# irrigation_control_unit.net
KiCad netlist of a schematic drawn in EAGLE
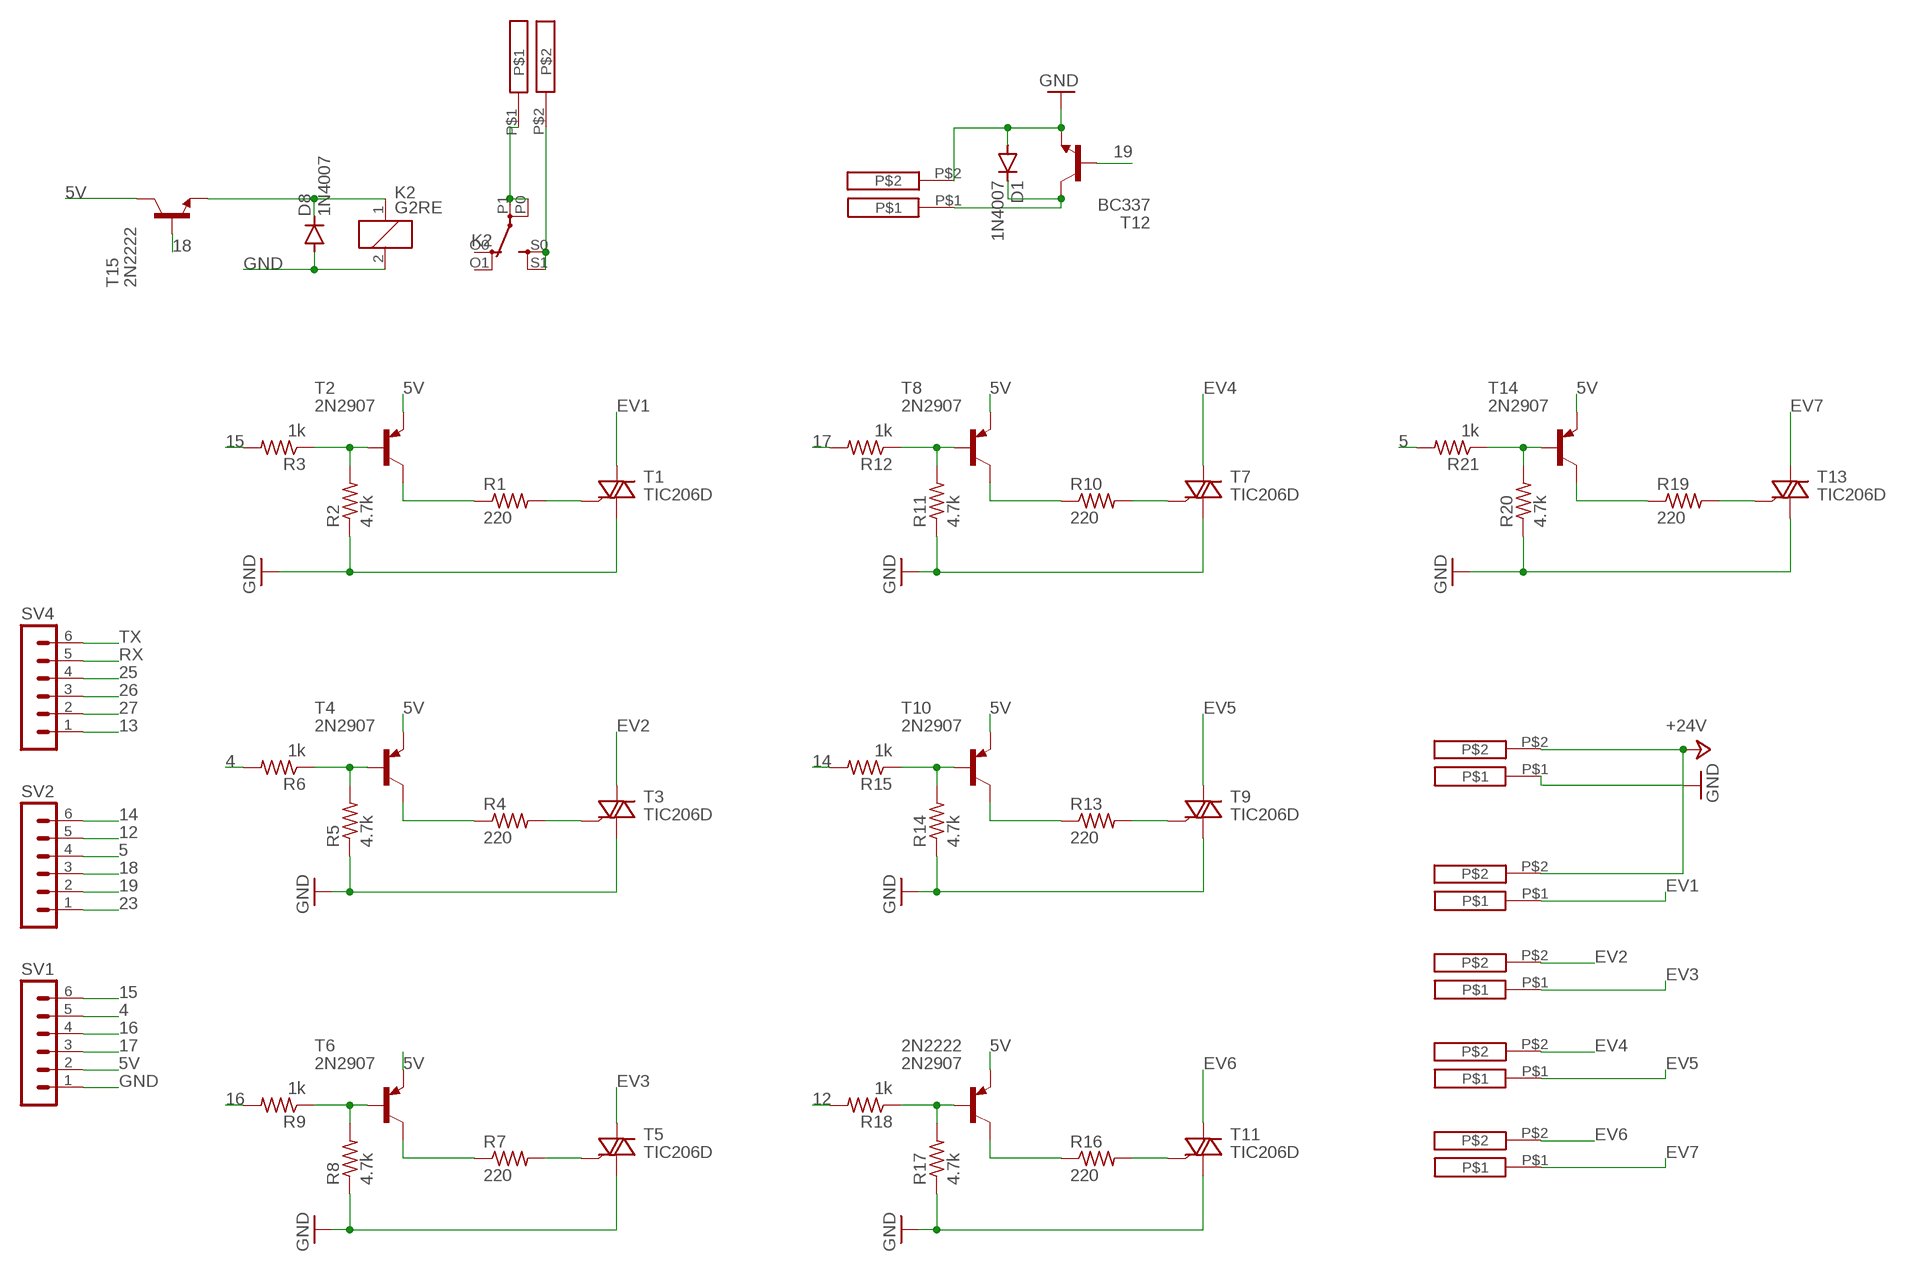
[diagram p0: schematic, sheet 1]

(export (version "E")
  (design (tool "Eeschema 10.0.6"))
  (components
    (comp (ref "2N2222")
      (value "2N2907")
      (footprint "eagle-import:TO92-EBC-OVAL")
      (libsource (lib "eagle-import") (part "2N2907"))
    )
    (comp (ref "D1")
      (value "1N4007")
      (footprint "eagle-import:DO35-7")
      (libsource (lib "eagle-import") (part "1N4148DO35-7"))
    )
    (comp (ref "D8")
      (value "1N4007")
      (footprint "eagle-import:DO35-7")
      (libsource (lib "eagle-import") (part "1N4148DO35-7"))
    )
    (comp (ref "K2")
      (value "G2RE")
      (footprint "eagle-import:G2RE")
      (libsource (lib "eagle-import") (part "G2RE"))
    )
    (comp (ref "R1")
      (value "220")
      (footprint "eagle-import:0204_7")
      (libsource (lib "eagle-import") (part "R-US_0204/7"))
    )
    (comp (ref "R2")
      (value "4.7k")
      (footprint "eagle-import:0204_7")
      (libsource (lib "eagle-import") (part "R-US_0204/7"))
    )
    (comp (ref "R3")
      (value "1k")
      (footprint "eagle-import:0204_7")
      (libsource (lib "eagle-import") (part "R-US_0204/7"))
    )
    (comp (ref "R4")
      (value "220")
      (footprint "eagle-import:0204_7")
      (libsource (lib "eagle-import") (part "R-US_0204/7"))
    )
    (comp (ref "R5")
      (value "4.7k")
      (footprint "eagle-import:0204_7")
      (libsource (lib "eagle-import") (part "R-US_0204/7"))
    )
    (comp (ref "R6")
      (value "1k")
      (footprint "eagle-import:0204_7")
      (libsource (lib "eagle-import") (part "R-US_0204/7"))
    )
    (comp (ref "R7")
      (value "220")
      (footprint "eagle-import:0204_7")
      (libsource (lib "eagle-import") (part "R-US_0204/7"))
    )
    (comp (ref "R8")
      (value "4.7k")
      (footprint "eagle-import:0204_7")
      (libsource (lib "eagle-import") (part "R-US_0204/7"))
    )
    (comp (ref "R9")
      (value "1k")
      (footprint "eagle-import:0204_7")
      (libsource (lib "eagle-import") (part "R-US_0204/7"))
    )
    (comp (ref "R10")
      (value "220")
      (footprint "eagle-import:0204_7")
      (libsource (lib "eagle-import") (part "R-US_0204/7"))
    )
    (comp (ref "R11")
      (value "4.7k")
      (footprint "eagle-import:0204_7")
      (libsource (lib "eagle-import") (part "R-US_0204/7"))
    )
    (comp (ref "R12")
      (value "1k")
      (footprint "eagle-import:0204_7")
      (libsource (lib "eagle-import") (part "R-US_0204/7"))
    )
    (comp (ref "R13")
      (value "220")
      (footprint "eagle-import:0204_7")
      (libsource (lib "eagle-import") (part "R-US_0204/7"))
    )
    (comp (ref "R14")
      (value "4.7k")
      (footprint "eagle-import:0204_7")
      (libsource (lib "eagle-import") (part "R-US_0204/7"))
    )
    (comp (ref "R15")
      (value "1k")
      (footprint "eagle-import:0204_7")
      (libsource (lib "eagle-import") (part "R-US_0204/7"))
    )
    (comp (ref "R16")
      (value "220")
      (footprint "eagle-import:0204_7")
      (libsource (lib "eagle-import") (part "R-US_0204/7"))
    )
    (comp (ref "R17")
      (value "4.7k")
      (footprint "eagle-import:0204_7")
      (libsource (lib "eagle-import") (part "R-US_0204/7"))
    )
    (comp (ref "R18")
      (value "1k")
      (footprint "eagle-import:0204_7")
      (libsource (lib "eagle-import") (part "R-US_0204/7"))
    )
    (comp (ref "R19")
      (value "220")
      (footprint "eagle-import:0204_7")
      (libsource (lib "eagle-import") (part "R-US_0204/7"))
    )
    (comp (ref "R20")
      (value "4.7k")
      (footprint "eagle-import:0204_7")
      (libsource (lib "eagle-import") (part "R-US_0204/7"))
    )
    (comp (ref "R21")
      (value "1k")
      (footprint "eagle-import:0204_7")
      (libsource (lib "eagle-import") (part "R-US_0204/7"))
    )
    (comp (ref "SV1")
      (value "MA06-1")
      (footprint "eagle-import:MA06-1")
      (libsource (lib "eagle-import") (part "MA06-1"))
    )
    (comp (ref "SV2")
      (value "MA06-1")
      (footprint "eagle-import:MA06-1")
      (libsource (lib "eagle-import") (part "MA06-1"))
    )
    (comp (ref "SV4")
      (value "MA06-1")
      (footprint "eagle-import:MA06-1")
      (libsource (lib "eagle-import") (part "MA06-1"))
    )
    (comp (ref "T1")
      (value "TIC206D")
      (footprint "eagle-import:TO220BV")
      (libsource (lib "eagle-import") (part "TIC206D"))
    )
    (comp (ref "T2")
      (value "2N2907")
      (footprint "eagle-import:TO92-EBC-OVAL")
      (libsource (lib "eagle-import") (part "2N2907"))
    )
    (comp (ref "T3")
      (value "TIC206D")
      (footprint "eagle-import:TO220BV")
      (libsource (lib "eagle-import") (part "TIC206D"))
    )
    (comp (ref "T4")
      (value "2N2907")
      (footprint "eagle-import:TO92-EBC-OVAL")
      (libsource (lib "eagle-import") (part "2N2907"))
    )
    (comp (ref "T5")
      (value "TIC206D")
      (footprint "eagle-import:TO220BV")
      (libsource (lib "eagle-import") (part "TIC206D"))
    )
    (comp (ref "T6")
      (value "2N2907")
      (footprint "eagle-import:TO92-EBC-OVAL")
      (libsource (lib "eagle-import") (part "2N2907"))
    )
    (comp (ref "T7")
      (value "TIC206D")
      (footprint "eagle-import:TO220BV")
      (libsource (lib "eagle-import") (part "TIC206D"))
    )
    (comp (ref "T8")
      (value "2N2907")
      (footprint "eagle-import:TO92-EBC-OVAL")
      (libsource (lib "eagle-import") (part "2N2907"))
    )
    (comp (ref "T9")
      (value "TIC206D")
      (footprint "eagle-import:TO220BV")
      (libsource (lib "eagle-import") (part "TIC206D"))
    )
    (comp (ref "T10")
      (value "2N2907")
      (footprint "eagle-import:TO92-EBC-OVAL")
      (libsource (lib "eagle-import") (part "2N2907"))
    )
    (comp (ref "T11")
      (value "TIC206D")
      (footprint "eagle-import:TO220BV")
      (libsource (lib "eagle-import") (part "TIC206D"))
    )
    (comp (ref "T12")
      (value "BC337")
      (footprint "eagle-import:TO92")
      (libsource (lib "eagle-import") (part "BC337"))
    )
    (comp (ref "T13")
      (value "TIC206D")
      (footprint "eagle-import:TO220BV")
      (libsource (lib "eagle-import") (part "TIC206D"))
    )
    (comp (ref "T14")
      (value "2N2907")
      (footprint "eagle-import:TO92-EBC-OVAL")
      (libsource (lib "eagle-import") (part "2N2907"))
    )
    (comp (ref "T15")
      (value "2N2222")
      (footprint "eagle-import:TO92-EBC-OVAL")
      (libsource (lib "eagle-import") (part "2N2222"))
    )
    (comp (ref "U$1")
      (value "2-PIN-7.5-CONNECTOR")
      (footprint "eagle-import:2-PIN-7.5-CONNECTOR")
      (libsource (lib "eagle-import") (part "2-PIN-7.5-CONNECTOR"))
    )
    (comp (ref "U$2")
      (value "2-PIN-7.5-CONNECTOR")
      (footprint "eagle-import:2-PIN-7.5-CONNECTOR")
      (libsource (lib "eagle-import") (part "2-PIN-7.5-CONNECTOR"))
    )
    (comp (ref "U$3")
      (value "2-PIN-7.5-CONNECTOR")
      (footprint "eagle-import:2-PIN-7.5-CONNECTOR")
      (libsource (lib "eagle-import") (part "2-PIN-7.5-CONNECTOR"))
    )
    (comp (ref "U$4")
      (value "2-PIN-7.5-CONNECTOR")
      (footprint "eagle-import:2-PIN-7.5-CONNECTOR")
      (libsource (lib "eagle-import") (part "2-PIN-7.5-CONNECTOR"))
    )
    (comp (ref "U$5")
      (value "2-PIN-7.5-CONNECTOR")
      (footprint "eagle-import:2-PIN-7.5-CONNECTOR")
      (libsource (lib "eagle-import") (part "2-PIN-7.5-CONNECTOR"))
    )
    (comp (ref "U$6")
      (value "2-PIN-7.5-CONNECTOR")
      (footprint "eagle-import:2-PIN-7.5-CONNECTOR")
      (libsource (lib "eagle-import") (part "2-PIN-7.5-CONNECTOR"))
    )
    (comp (ref "U$7")
      (value "2-PIN-7.5-CONNECTOR")
      (footprint "eagle-import:2-PIN-7.5-CONNECTOR")
      (libsource (lib "eagle-import") (part "2-PIN-7.5-CONNECTOR"))
    )
  )
  (nets
    (net (code "1") (name "+24V") (class "Default")
      (node (ref "U$1") (pin "P$2") (pinfunction "P$2_P$2") (pintype "bidirectional"))
      (node (ref "U$2") (pin "P$2") (pinfunction "P$2_P$2") (pintype "bidirectional"))
    )
    (net (code "2") (name "/4") (class "Default")
      (node (ref "R6") (pin "2") (pinfunction "2_2") (pintype "passive"))
      (node (ref "SV1") (pin "5") (pinfunction "5_5") (pintype "passive"))
    )
    (net (code "3") (name "/5") (class "Default")
      (node (ref "R21") (pin "2") (pinfunction "2_2") (pintype "passive"))
      (node (ref "SV2") (pin "4") (pinfunction "4_4") (pintype "passive"))
    )
    (net (code "4") (name "/5V") (class "Default")
      (node (ref "2N2222") (pin "E") (pinfunction "E_E") (pintype "passive"))
      (node (ref "SV1") (pin "2") (pinfunction "2_2") (pintype "passive"))
      (node (ref "T10") (pin "E") (pinfunction "E_E") (pintype "passive"))
      (node (ref "T14") (pin "E") (pinfunction "E_E") (pintype "passive"))
      (node (ref "T15") (pin "C") (pinfunction "C_C") (pintype "passive"))
      (node (ref "T2") (pin "E") (pinfunction "E_E") (pintype "passive"))
      (node (ref "T4") (pin "E") (pinfunction "E_E") (pintype "passive"))
      (node (ref "T6") (pin "E") (pinfunction "E_E") (pintype "passive"))
      (node (ref "T8") (pin "E") (pinfunction "E_E") (pintype "passive"))
    )
    (net (code "5") (name "/12") (class "Default")
      (node (ref "R18") (pin "2") (pinfunction "2_2") (pintype "passive"))
      (node (ref "SV2") (pin "5") (pinfunction "5_5") (pintype "passive"))
    )
    (net (code "6") (name "/13") (class "Default")
      (node (ref "SV4") (pin "1") (pinfunction "1_1") (pintype "passive"))
    )
    (net (code "7") (name "/14") (class "Default")
      (node (ref "R15") (pin "2") (pinfunction "2_2") (pintype "passive"))
      (node (ref "SV2") (pin "6") (pinfunction "6_6") (pintype "passive"))
    )
    (net (code "8") (name "/15") (class "Default")
      (node (ref "R3") (pin "2") (pinfunction "2_2") (pintype "passive"))
      (node (ref "SV1") (pin "6") (pinfunction "6_6") (pintype "passive"))
    )
    (net (code "9") (name "/16") (class "Default")
      (node (ref "R9") (pin "2") (pinfunction "2_2") (pintype "passive"))
      (node (ref "SV1") (pin "4") (pinfunction "4_4") (pintype "passive"))
    )
    (net (code "10") (name "/17") (class "Default")
      (node (ref "R12") (pin "2") (pinfunction "2_2") (pintype "passive"))
      (node (ref "SV1") (pin "3") (pinfunction "3_3") (pintype "passive"))
    )
    (net (code "11") (name "/18") (class "Default")
      (node (ref "SV2") (pin "3") (pinfunction "3_3") (pintype "passive"))
      (node (ref "T15") (pin "B") (pinfunction "B_B") (pintype "passive"))
    )
    (net (code "12") (name "/19") (class "Default")
      (node (ref "SV2") (pin "2") (pinfunction "2_2") (pintype "passive"))
      (node (ref "T12") (pin "2") (pinfunction "B_2") (pintype "passive"))
    )
    (net (code "13") (name "/23") (class "Default")
      (node (ref "SV2") (pin "1") (pinfunction "1_1") (pintype "passive"))
    )
    (net (code "14") (name "/25") (class "Default")
      (node (ref "SV4") (pin "4") (pinfunction "4_4") (pintype "passive"))
    )
    (net (code "15") (name "/26") (class "Default")
      (node (ref "SV4") (pin "3") (pinfunction "3_3") (pintype "passive"))
    )
    (net (code "16") (name "/27") (class "Default")
      (node (ref "SV4") (pin "2") (pinfunction "2_2") (pintype "passive"))
    )
    (net (code "17") (name "/EV1") (class "Default")
      (node (ref "T1") (pin "T2") (pinfunction "A2_T2") (pintype "passive"))
      (node (ref "U$2") (pin "P$1") (pinfunction "P$1_P$1") (pintype "bidirectional"))
    )
    (net (code "18") (name "/EV2") (class "Default")
      (node (ref "T3") (pin "T2") (pinfunction "A2_T2") (pintype "passive"))
      (node (ref "U$3") (pin "P$2") (pinfunction "P$2_P$2") (pintype "bidirectional"))
    )
    (net (code "19") (name "/EV3") (class "Default")
      (node (ref "T5") (pin "T2") (pinfunction "A2_T2") (pintype "passive"))
      (node (ref "U$3") (pin "P$1") (pinfunction "P$1_P$1") (pintype "bidirectional"))
    )
    (net (code "20") (name "/EV4") (class "Default")
      (node (ref "T7") (pin "T2") (pinfunction "A2_T2") (pintype "passive"))
      (node (ref "U$4") (pin "P$2") (pinfunction "P$2_P$2") (pintype "bidirectional"))
    )
    (net (code "21") (name "/EV5") (class "Default")
      (node (ref "T9") (pin "T2") (pinfunction "A2_T2") (pintype "passive"))
      (node (ref "U$4") (pin "P$1") (pinfunction "P$1_P$1") (pintype "bidirectional"))
    )
    (net (code "22") (name "/EV6") (class "Default")
      (node (ref "T11") (pin "T2") (pinfunction "A2_T2") (pintype "passive"))
      (node (ref "U$5") (pin "P$2") (pinfunction "P$2_P$2") (pintype "bidirectional"))
    )
    (net (code "23") (name "/EV7") (class "Default")
      (node (ref "T13") (pin "T2") (pinfunction "A2_T2") (pintype "passive"))
      (node (ref "U$5") (pin "P$1") (pinfunction "P$1_P$1") (pintype "bidirectional"))
    )
    (net (code "24") (name "/RX") (class "Default")
      (node (ref "SV4") (pin "5") (pinfunction "5_5") (pintype "passive"))
    )
    (net (code "25") (name "/TX") (class "Default")
      (node (ref "SV4") (pin "6") (pinfunction "6_6") (pintype "passive"))
    )
    (net (code "26") (name "GND") (class "Default")
      (node (ref "D1") (pin "A") (pinfunction "A_A") (pintype "passive"))
      (node (ref "D8") (pin "A") (pinfunction "A_A") (pintype "passive"))
      (node (ref "K2") (pin "2") (pinfunction "2_2") (pintype "passive"))
      (node (ref "R11") (pin "1") (pinfunction "1_1") (pintype "passive"))
      (node (ref "R14") (pin "1") (pinfunction "1_1") (pintype "passive"))
      (node (ref "R17") (pin "1") (pinfunction "1_1") (pintype "passive"))
      (node (ref "R2") (pin "1") (pinfunction "1_1") (pintype "passive"))
      (node (ref "R20") (pin "1") (pinfunction "1_1") (pintype "passive"))
      (node (ref "R5") (pin "1") (pinfunction "1_1") (pintype "passive"))
      (node (ref "R8") (pin "1") (pinfunction "1_1") (pintype "passive"))
      (node (ref "SV1") (pin "1") (pinfunction "1_1") (pintype "passive"))
      (node (ref "T1") (pin "T1") (pinfunction "A1_T1") (pintype "passive"))
      (node (ref "T11") (pin "T1") (pinfunction "A1_T1") (pintype "passive"))
      (node (ref "T12") (pin "1") (pinfunction "E_1") (pintype "passive"))
      (node (ref "T13") (pin "T1") (pinfunction "A1_T1") (pintype "passive"))
      (node (ref "T3") (pin "T1") (pinfunction "A1_T1") (pintype "passive"))
      (node (ref "T5") (pin "T1") (pinfunction "A1_T1") (pintype "passive"))
      (node (ref "T7") (pin "T1") (pinfunction "A1_T1") (pintype "passive"))
      (node (ref "T9") (pin "T1") (pinfunction "A1_T1") (pintype "passive"))
      (node (ref "U$1") (pin "P$1") (pinfunction "P$1_P$1") (pintype "bidirectional"))
      (node (ref "U$7") (pin "P$2") (pinfunction "P$2_P$2") (pintype "bidirectional"))
    )
    (net (code "27") (name "Net-(2N2222-PadB)") (class "Default")
      (node (ref "2N2222") (pin "B") (pinfunction "B_B") (pintype "passive"))
      (node (ref "R17") (pin "2") (pinfunction "2_2") (pintype "passive"))
      (node (ref "R18") (pin "1") (pinfunction "1_1") (pintype "passive"))
    )
    (net (code "28") (name "Net-(2N2222-PadC)") (class "Default")
      (node (ref "2N2222") (pin "C") (pinfunction "C_C") (pintype "passive"))
      (node (ref "R16") (pin "1") (pinfunction "1_1") (pintype "passive"))
    )
    (net (code "29") (name "Net-(D8-PadC)") (class "Default")
      (node (ref "D8") (pin "C") (pinfunction "C_C") (pintype "passive"))
      (node (ref "K2") (pin "1") (pinfunction "1_1") (pintype "passive"))
      (node (ref "T15") (pin "E") (pinfunction "E_E") (pintype "passive"))
    )
    (net (code "30") (name "Net-(K2B-P-PadP0)") (class "Default")
      (node (ref "K2") (pin "P0") (pinfunction "P_P0") (pintype "passive"))
      (node (ref "K2") (pin "P1") (pinfunction "P_P1") (pintype "passive"))
      (node (ref "U$6") (pin "P$1") (pinfunction "P$1_P$1") (pintype "bidirectional"))
    )
    (net (code "31") (name "Net-(K2B-S-PadS0)") (class "Default")
      (node (ref "K2") (pin "S0") (pinfunction "S_S0") (pintype "passive"))
      (node (ref "K2") (pin "S1") (pinfunction "S_S1") (pintype "passive"))
      (node (ref "U$6") (pin "P$2") (pinfunction "P$2_P$2") (pintype "bidirectional"))
    )
    (net (code "32") (name "Net-(R1-Pad1)") (class "Default")
      (node (ref "R1") (pin "1") (pinfunction "1_1") (pintype "passive"))
      (node (ref "T2") (pin "C") (pinfunction "C_C") (pintype "passive"))
    )
    (net (code "33") (name "Net-(R1-Pad2)") (class "Default")
      (node (ref "R1") (pin "2") (pinfunction "2_2") (pintype "passive"))
      (node (ref "T1") (pin "G") (pinfunction "G_G") (pintype "passive"))
    )
    (net (code "34") (name "Net-(R2-Pad2)") (class "Default")
      (node (ref "R2") (pin "2") (pinfunction "2_2") (pintype "passive"))
      (node (ref "R3") (pin "1") (pinfunction "1_1") (pintype "passive"))
      (node (ref "T2") (pin "B") (pinfunction "B_B") (pintype "passive"))
    )
    (net (code "35") (name "Net-(R4-Pad1)") (class "Default")
      (node (ref "R4") (pin "1") (pinfunction "1_1") (pintype "passive"))
      (node (ref "T4") (pin "C") (pinfunction "C_C") (pintype "passive"))
    )
    (net (code "36") (name "Net-(R4-Pad2)") (class "Default")
      (node (ref "R4") (pin "2") (pinfunction "2_2") (pintype "passive"))
      (node (ref "T3") (pin "G") (pinfunction "G_G") (pintype "passive"))
    )
    (net (code "37") (name "Net-(R5-Pad2)") (class "Default")
      (node (ref "R5") (pin "2") (pinfunction "2_2") (pintype "passive"))
      (node (ref "R6") (pin "1") (pinfunction "1_1") (pintype "passive"))
      (node (ref "T4") (pin "B") (pinfunction "B_B") (pintype "passive"))
    )
    (net (code "38") (name "Net-(R7-Pad1)") (class "Default")
      (node (ref "R7") (pin "1") (pinfunction "1_1") (pintype "passive"))
      (node (ref "T6") (pin "C") (pinfunction "C_C") (pintype "passive"))
    )
    (net (code "39") (name "Net-(R7-Pad2)") (class "Default")
      (node (ref "R7") (pin "2") (pinfunction "2_2") (pintype "passive"))
      (node (ref "T5") (pin "G") (pinfunction "G_G") (pintype "passive"))
    )
    (net (code "40") (name "Net-(R8-Pad2)") (class "Default")
      (node (ref "R8") (pin "2") (pinfunction "2_2") (pintype "passive"))
      (node (ref "R9") (pin "1") (pinfunction "1_1") (pintype "passive"))
      (node (ref "T6") (pin "B") (pinfunction "B_B") (pintype "passive"))
    )
    (net (code "41") (name "Net-(R10-Pad1)") (class "Default")
      (node (ref "R10") (pin "1") (pinfunction "1_1") (pintype "passive"))
      (node (ref "T8") (pin "C") (pinfunction "C_C") (pintype "passive"))
    )
    (net (code "42") (name "Net-(R10-Pad2)") (class "Default")
      (node (ref "R10") (pin "2") (pinfunction "2_2") (pintype "passive"))
      (node (ref "T7") (pin "G") (pinfunction "G_G") (pintype "passive"))
    )
    (net (code "43") (name "Net-(R11-Pad2)") (class "Default")
      (node (ref "R11") (pin "2") (pinfunction "2_2") (pintype "passive"))
      (node (ref "R12") (pin "1") (pinfunction "1_1") (pintype "passive"))
      (node (ref "T8") (pin "B") (pinfunction "B_B") (pintype "passive"))
    )
    (net (code "44") (name "Net-(R13-Pad1)") (class "Default")
      (node (ref "R13") (pin "1") (pinfunction "1_1") (pintype "passive"))
      (node (ref "T10") (pin "C") (pinfunction "C_C") (pintype "passive"))
    )
    (net (code "45") (name "Net-(R13-Pad2)") (class "Default")
      (node (ref "R13") (pin "2") (pinfunction "2_2") (pintype "passive"))
      (node (ref "T9") (pin "G") (pinfunction "G_G") (pintype "passive"))
    )
    (net (code "46") (name "Net-(R14-Pad2)") (class "Default")
      (node (ref "R14") (pin "2") (pinfunction "2_2") (pintype "passive"))
      (node (ref "R15") (pin "1") (pinfunction "1_1") (pintype "passive"))
      (node (ref "T10") (pin "B") (pinfunction "B_B") (pintype "passive"))
    )
    (net (code "47") (name "Net-(R16-Pad2)") (class "Default")
      (node (ref "R16") (pin "2") (pinfunction "2_2") (pintype "passive"))
      (node (ref "T11") (pin "G") (pinfunction "G_G") (pintype "passive"))
    )
    (net (code "48") (name "Net-(R19-Pad1)") (class "Default")
      (node (ref "R19") (pin "1") (pinfunction "1_1") (pintype "passive"))
      (node (ref "T14") (pin "C") (pinfunction "C_C") (pintype "passive"))
    )
    (net (code "49") (name "Net-(R19-Pad2)") (class "Default")
      (node (ref "R19") (pin "2") (pinfunction "2_2") (pintype "passive"))
      (node (ref "T13") (pin "G") (pinfunction "G_G") (pintype "passive"))
    )
    (net (code "50") (name "Net-(R20-Pad2)") (class "Default")
      (node (ref "R20") (pin "2") (pinfunction "2_2") (pintype "passive"))
      (node (ref "R21") (pin "1") (pinfunction "1_1") (pintype "passive"))
      (node (ref "T14") (pin "B") (pinfunction "B_B") (pintype "passive"))
    )
    (net (code "51") (name "Net-(T12-C)") (class "Default")
      (node (ref "D1") (pin "C") (pinfunction "C_C") (pintype "passive"))
      (node (ref "T12") (pin "3") (pinfunction "C_3") (pintype "passive"))
      (node (ref "U$7") (pin "P$1") (pinfunction "P$1_P$1") (pintype "bidirectional"))
    )
    (net (code "52") (name "unconnected-(K2B-O-PadO0)") (class "Default")
      (node (ref "K2") (pin "O0") (pinfunction "O_O0") (pintype "passive"))
    )
    (net (code "53") (name "unconnected-(K2B-O-PadO1)") (class "Default")
      (node (ref "K2") (pin "O1") (pinfunction "O_O1") (pintype "passive"))
    )
  )
)
